# shield.net
KiCad netlist of a schematic drawn in EAGLE
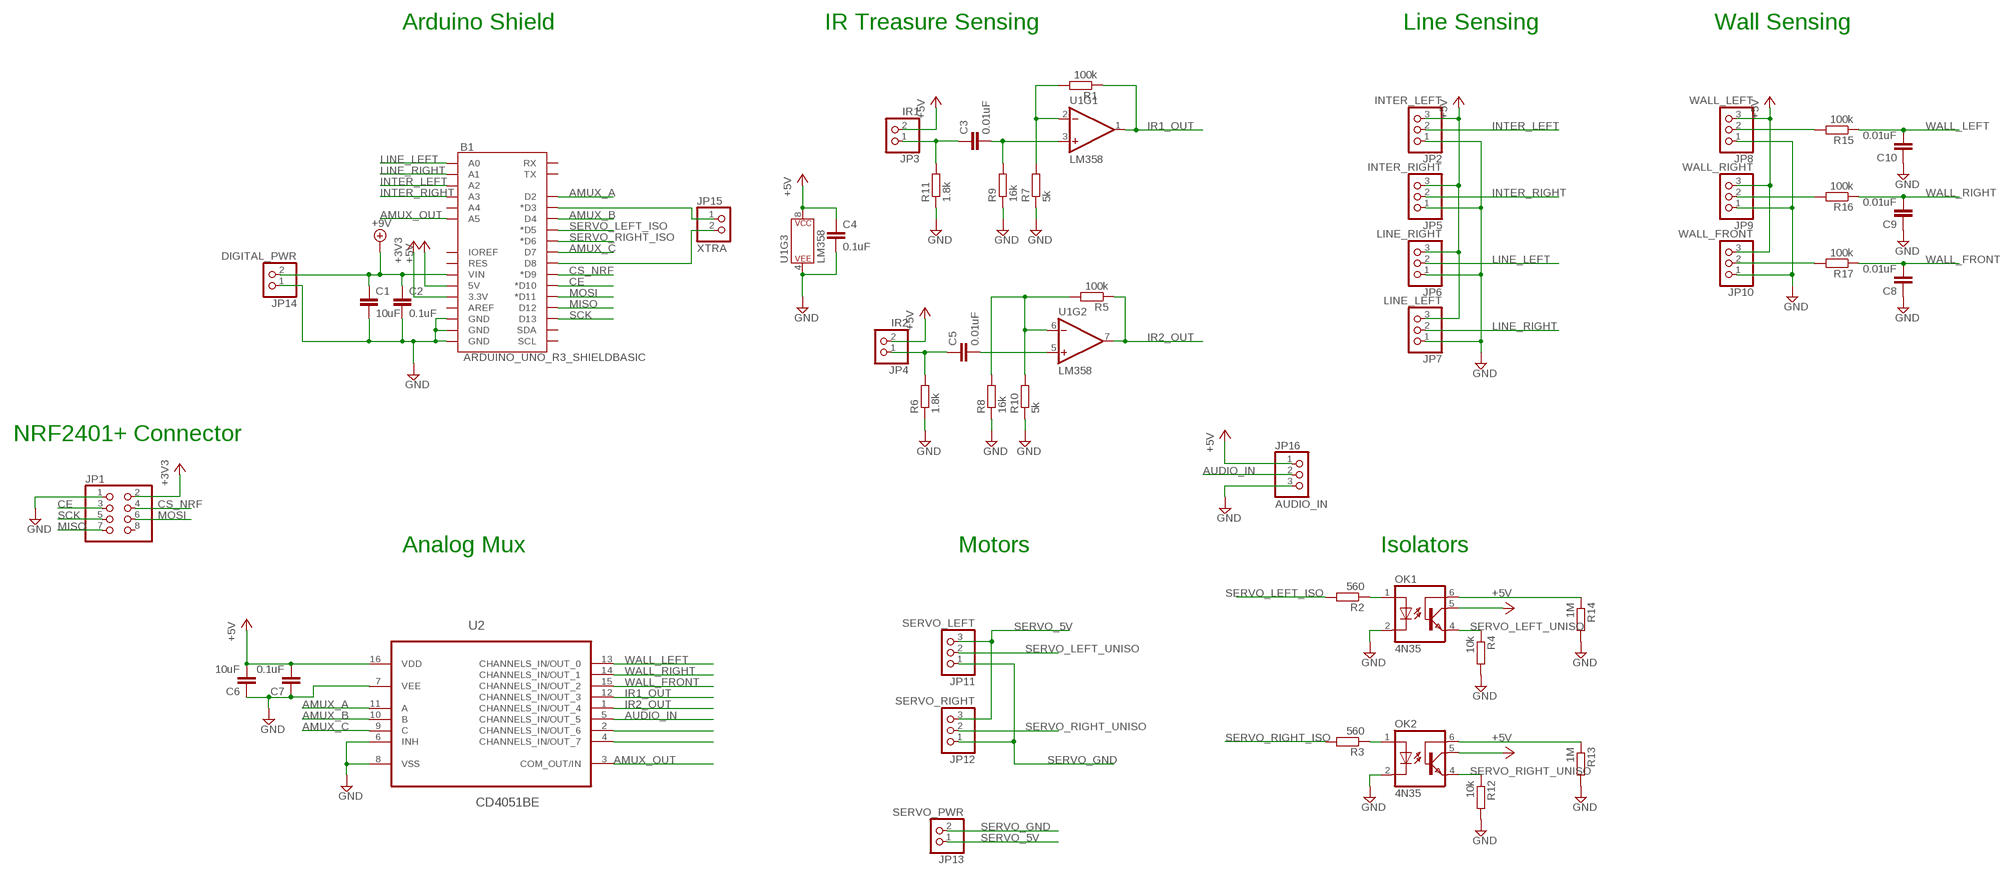
[diagram p0: schematic, sheet 1]

(export (version "E")
  (design (tool "Eeschema 10.0.6"))
  (components
    (comp (ref "B1")
      (value "ARDUINO_UNO_R3_SHIELDBASIC")
      (footprint "eagle-import:UNO_R3_SHIELD")
      (libsource (lib "eagle-import") (part "ARDUINO_UNO_R3_SHIELDBASIC"))
    )
    (comp (ref "C1")
      (value "10uF")
      (footprint "eagle-import:C5B3")
      (libsource (lib "eagle-import") (part "C5/3"))
    )
    (comp (ref "C2")
      (value "0.1uF")
      (footprint "eagle-import:C5B3")
      (libsource (lib "eagle-import") (part "C5/3"))
    )
    (comp (ref "C3")
      (value "0.01uF")
      (footprint "eagle-import:C5B3")
      (libsource (lib "eagle-import") (part "C5/3"))
    )
    (comp (ref "C4")
      (value "0.1uF")
      (footprint "eagle-import:C2.5-2")
      (libsource (lib "eagle-import") (part "C2.5/2"))
    )
    (comp (ref "C5")
      (value "0.01uF")
      (footprint "eagle-import:C5B3")
      (libsource (lib "eagle-import") (part "C5/3"))
    )
    (comp (ref "C6")
      (value "10uF")
      (footprint "eagle-import:C5B3")
      (libsource (lib "eagle-import") (part "C5/3"))
    )
    (comp (ref "C7")
      (value "0.1uF")
      (footprint "eagle-import:C5B3")
      (libsource (lib "eagle-import") (part "C5/3"))
    )
    (comp (ref "C8")
      (value "0.01uF")
      (footprint "eagle-import:C5B3")
      (libsource (lib "eagle-import") (part "C5/3"))
    )
    (comp (ref "C9")
      (value "0.01uF")
      (footprint "eagle-import:C5B3")
      (libsource (lib "eagle-import") (part "C5/3"))
    )
    (comp (ref "C10")
      (value "0.01uF")
      (footprint "eagle-import:C5B3")
      (libsource (lib "eagle-import") (part "C5/3"))
    )
    (comp (ref "JP1")
      (value "PINHD-2X4")
      (footprint "eagle-import:2X04")
      (libsource (lib "eagle-import") (part "PINHD-2X4"))
    )
    (comp (ref "JP2")
      (value "INTER_LEFT")
      (footprint "eagle-import:1X03")
      (libsource (lib "eagle-import") (part "PINHD-1X3"))
    )
    (comp (ref "JP3")
      (value "IR1")
      (footprint "eagle-import:1X02")
      (libsource (lib "eagle-import") (part "PINHD-1X2"))
    )
    (comp (ref "JP4")
      (value "IR2")
      (footprint "eagle-import:1X02")
      (libsource (lib "eagle-import") (part "PINHD-1X2"))
    )
    (comp (ref "JP5")
      (value "INTER_RIGHT")
      (footprint "eagle-import:1X03")
      (libsource (lib "eagle-import") (part "PINHD-1X3"))
    )
    (comp (ref "JP6")
      (value "LINE_RIGHT")
      (footprint "eagle-import:1X03")
      (libsource (lib "eagle-import") (part "PINHD-1X3"))
    )
    (comp (ref "JP7")
      (value "LINE_LEFT")
      (footprint "eagle-import:1X03")
      (libsource (lib "eagle-import") (part "PINHD-1X3"))
    )
    (comp (ref "JP8")
      (value "WALL_LEFT")
      (footprint "eagle-import:1X03")
      (libsource (lib "eagle-import") (part "PINHD-1X3"))
    )
    (comp (ref "JP9")
      (value "WALL_RIGHT")
      (footprint "eagle-import:1X03")
      (libsource (lib "eagle-import") (part "PINHD-1X3"))
    )
    (comp (ref "JP10")
      (value "WALL_FRONT")
      (footprint "eagle-import:1X03")
      (libsource (lib "eagle-import") (part "PINHD-1X3"))
    )
    (comp (ref "JP11")
      (value "SERVO_LEFT")
      (footprint "eagle-import:1X03")
      (libsource (lib "eagle-import") (part "PINHD-1X3"))
    )
    (comp (ref "JP12")
      (value "SERVO_RIGHT")
      (footprint "eagle-import:1X03")
      (libsource (lib "eagle-import") (part "PINHD-1X3"))
    )
    (comp (ref "JP13")
      (value "SERVO_PWR")
      (footprint "eagle-import:1X02")
      (libsource (lib "eagle-import") (part "PINHD-1X2"))
    )
    (comp (ref "JP14")
      (value "DIGITAL_PWR")
      (footprint "eagle-import:1X02")
      (libsource (lib "eagle-import") (part "PINHD-1X2"))
    )
    (comp (ref "JP15")
      (value "XTRA")
      (footprint "eagle-import:1X02")
      (libsource (lib "eagle-import") (part "PINHD-1X2"))
    )
    (comp (ref "JP16")
      (value "AUDIO_IN")
      (footprint "eagle-import:1X03")
      (libsource (lib "eagle-import") (part "PINHD-1X3"))
    )
    (comp (ref "OK1")
      (value "4N35")
      (footprint "eagle-import:DIL06")
      (fields (field (name "MF") "FAIRCHILD SEMICONDUCTOR"))
      (libsource (lib "eagle-import") (part "4N35"))
    )
    (comp (ref "OK2")
      (value "4N35")
      (footprint "eagle-import:DIL06")
      (fields (field (name "MF") "FAIRCHILD SEMICONDUCTOR"))
      (libsource (lib "eagle-import") (part "4N35"))
    )
    (comp (ref "R1")
      (value "100k")
      (footprint "eagle-import:VMTA55")
      (libsource (lib "eagle-import") (part "R-EU_VMTA55"))
    )
    (comp (ref "R2")
      (value "560")
      (footprint "eagle-import:VMTA55")
      (libsource (lib "eagle-import") (part "R-EU_VMTA55"))
    )
    (comp (ref "R3")
      (value "560")
      (footprint "eagle-import:VMTA55")
      (libsource (lib "eagle-import") (part "R-EU_VMTA55"))
    )
    (comp (ref "R4")
      (value "10k")
      (footprint "eagle-import:VMTA55")
      (libsource (lib "eagle-import") (part "R-EU_VMTA55"))
    )
    (comp (ref "R5")
      (value "100k")
      (footprint "eagle-import:VMTA55")
      (libsource (lib "eagle-import") (part "R-EU_VMTA55"))
    )
    (comp (ref "R6")
      (value "1.8k")
      (footprint "eagle-import:VMTA55")
      (libsource (lib "eagle-import") (part "R-EU_VMTA55"))
    )
    (comp (ref "R7")
      (value "5k")
      (footprint "eagle-import:VMTA55")
      (libsource (lib "eagle-import") (part "R-EU_VMTA55"))
    )
    (comp (ref "R8")
      (value "16k")
      (footprint "eagle-import:VMTA55")
      (libsource (lib "eagle-import") (part "R-EU_VMTA55"))
    )
    (comp (ref "R9")
      (value "16k")
      (footprint "eagle-import:VMTA55")
      (libsource (lib "eagle-import") (part "R-EU_VMTA55"))
    )
    (comp (ref "R10")
      (value "5k")
      (footprint "eagle-import:VMTA55")
      (libsource (lib "eagle-import") (part "R-EU_VMTA55"))
    )
    (comp (ref "R11")
      (value "1.8k")
      (footprint "eagle-import:VMTA55")
      (libsource (lib "eagle-import") (part "R-EU_VMTA55"))
    )
    (comp (ref "R12")
      (value "10k")
      (footprint "eagle-import:VMTA55")
      (libsource (lib "eagle-import") (part "R-EU_VMTA55"))
    )
    (comp (ref "R13")
      (value "1M")
      (footprint "eagle-import:VMTA55")
      (libsource (lib "eagle-import") (part "R-EU_VMTA55"))
    )
    (comp (ref "R14")
      (value "1M")
      (footprint "eagle-import:VMTA55")
      (libsource (lib "eagle-import") (part "R-EU_VMTA55"))
    )
    (comp (ref "R15")
      (value "100k")
      (footprint "eagle-import:VMTA55")
      (libsource (lib "eagle-import") (part "R-EU_VMTA55"))
    )
    (comp (ref "R16")
      (value "100k")
      (footprint "eagle-import:VMTA55")
      (libsource (lib "eagle-import") (part "R-EU_VMTA55"))
    )
    (comp (ref "R17")
      (value "100k")
      (footprint "eagle-import:VMTA55")
      (libsource (lib "eagle-import") (part "R-EU_VMTA55"))
    )
    (comp (ref "U1")
      (value "LM358")
      (footprint "eagle-import:DIP08")
      (libsource (lib "eagle-import") (part "LM358"))
    )
    (comp (ref "U2")
      (value "CD4051BE")
      (footprint "eagle-import:DIP254P762X508-16")
      (libsource (lib "eagle-import") (part "CD4051BE"))
    )
  )
  (nets
    (net (code "1") (name "+3V3") (class "Default")
      (node (ref "B1") (pin "3.3V") (pinfunction "3.3V_3.3V") (pintype "bidirectional"))
      (node (ref "JP1") (pin "2") (pinfunction "2_2") (pintype "passive"))
    )
    (net (code "2") (name "+5V") (class "Default")
      (node (ref "B1") (pin "5V") (pinfunction "5V_5V") (pintype "bidirectional"))
      (node (ref "C4") (pin "1") (pinfunction "1_1") (pintype "passive"))
      (node (ref "C6") (pin "2") (pinfunction "2_2") (pintype "passive"))
      (node (ref "C7") (pin "2") (pinfunction "2_2") (pintype "passive"))
      (node (ref "JP10") (pin "3") (pinfunction "3_3") (pintype "passive"))
      (node (ref "JP16") (pin "1") (pinfunction "1_1") (pintype "passive"))
      (node (ref "JP2") (pin "3") (pinfunction "3_3") (pintype "passive"))
      (node (ref "JP3") (pin "2") (pinfunction "2_2") (pintype "passive"))
      (node (ref "JP4") (pin "2") (pinfunction "2_2") (pintype "passive"))
      (node (ref "JP5") (pin "3") (pinfunction "3_3") (pintype "passive"))
      (node (ref "JP6") (pin "3") (pinfunction "3_3") (pintype "passive"))
      (node (ref "JP7") (pin "3") (pinfunction "3_3") (pintype "passive"))
      (node (ref "JP8") (pin "3") (pinfunction "3_3") (pintype "passive"))
      (node (ref "JP9") (pin "3") (pinfunction "3_3") (pintype "passive"))
      (node (ref "OK1") (pin "5") (pinfunction "COL_5") (pintype "passive"))
      (node (ref "OK2") (pin "5") (pinfunction "COL_5") (pintype "passive"))
      (node (ref "U1") (pin "8") (pinfunction "P$V+_8") (pintype "bidirectional"))
      (node (ref "U2") (pin "16") (pinfunction "VDD_16") (pintype "power_in"))
    )
    (net (code "3") (name "+9V") (class "Default")
      (node (ref "B1") (pin "VIN") (pinfunction "VIN_VIN") (pintype "bidirectional"))
      (node (ref "C1") (pin "1") (pinfunction "1_1") (pintype "passive"))
      (node (ref "C2") (pin "1") (pinfunction "1_1") (pintype "passive"))
      (node (ref "JP14") (pin "2") (pinfunction "2_2") (pintype "passive"))
    )
    (net (code "4") (name "/AMUX_A") (class "Default")
      (node (ref "B1") (pin "D2") (pinfunction "D2_D2") (pintype "bidirectional"))
      (node (ref "U2") (pin "11") (pinfunction "A_11") (pintype "input"))
    )
    (net (code "5") (name "/AMUX_B") (class "Default")
      (node (ref "B1") (pin "D4") (pinfunction "D4_D4") (pintype "bidirectional"))
      (node (ref "U2") (pin "10") (pinfunction "B_10") (pintype "input"))
    )
    (net (code "6") (name "/AMUX_C") (class "Default")
      (node (ref "B1") (pin "D7") (pinfunction "D7_D7") (pintype "bidirectional"))
      (node (ref "U2") (pin "9") (pinfunction "C_9") (pintype "input"))
    )
    (net (code "7") (name "/AMUX_OUT") (class "Default")
      (node (ref "B1") (pin "A5") (pinfunction "A5_A5") (pintype "bidirectional"))
      (node (ref "U2") (pin "3") (pinfunction "COM_OUT/IN_3") (pintype "bidirectional"))
    )
    (net (code "8") (name "/AUDIO_IN") (class "Default")
      (node (ref "JP16") (pin "2") (pinfunction "2_2") (pintype "passive"))
      (node (ref "U2") (pin "5") (pinfunction "CHANNELS_IN/OUT_5_5") (pintype "bidirectional"))
    )
    (net (code "9") (name "/CE") (class "Default")
      (node (ref "B1") (pin "D10") (pinfunction "*D10_D10") (pintype "bidirectional"))
      (node (ref "JP1") (pin "3") (pinfunction "3_3") (pintype "passive"))
    )
    (net (code "10") (name "/CS_NRF") (class "Default")
      (node (ref "B1") (pin "D9") (pinfunction "*D9_D9") (pintype "bidirectional"))
      (node (ref "JP1") (pin "4") (pinfunction "4_4") (pintype "passive"))
    )
    (net (code "11") (name "/INTER_LEFT") (class "Default")
      (node (ref "B1") (pin "A2") (pinfunction "A2_A2") (pintype "bidirectional"))
      (node (ref "JP2") (pin "2") (pinfunction "2_2") (pintype "passive"))
    )
    (net (code "12") (name "/INTER_RIGHT") (class "Default")
      (node (ref "B1") (pin "A3") (pinfunction "A3_A3") (pintype "bidirectional"))
      (node (ref "JP5") (pin "2") (pinfunction "2_2") (pintype "passive"))
    )
    (net (code "13") (name "/IR1_OUT") (class "Default")
      (node (ref "R1") (pin "1") (pinfunction "1_1") (pintype "passive"))
      (node (ref "U1") (pin "1") (pinfunction "OUT_1") (pintype "output"))
      (node (ref "U2") (pin "12") (pinfunction "CHANNELS_IN/OUT_3_12") (pintype "bidirectional"))
    )
    (net (code "14") (name "/IR2_OUT") (class "Default")
      (node (ref "R5") (pin "1") (pinfunction "1_1") (pintype "passive"))
      (node (ref "U1") (pin "7") (pinfunction "OUT_7") (pintype "output"))
      (node (ref "U2") (pin "1") (pinfunction "CHANNELS_IN/OUT_4_1") (pintype "bidirectional"))
    )
    (net (code "15") (name "/LINE_LEFT") (class "Default")
      (node (ref "B1") (pin "A0") (pinfunction "A0_A0") (pintype "bidirectional"))
      (node (ref "JP6") (pin "2") (pinfunction "2_2") (pintype "passive"))
    )
    (net (code "16") (name "/LINE_RIGHT") (class "Default")
      (node (ref "B1") (pin "A1") (pinfunction "A1_A1") (pintype "bidirectional"))
      (node (ref "JP7") (pin "2") (pinfunction "2_2") (pintype "passive"))
    )
    (net (code "17") (name "/MISO") (class "Default")
      (node (ref "B1") (pin "D12") (pinfunction "D12_D12") (pintype "bidirectional"))
      (node (ref "JP1") (pin "7") (pinfunction "7_7") (pintype "passive"))
    )
    (net (code "18") (name "/MOSI") (class "Default")
      (node (ref "B1") (pin "D11") (pinfunction "*D11_D11") (pintype "bidirectional"))
      (node (ref "JP1") (pin "6") (pinfunction "6_6") (pintype "passive"))
    )
    (net (code "19") (name "/SCK") (class "Default")
      (node (ref "B1") (pin "D13") (pinfunction "D13_D13") (pintype "bidirectional"))
      (node (ref "JP1") (pin "5") (pinfunction "5_5") (pintype "passive"))
    )
    (net (code "20") (name "/SERVO_5V") (class "Default")
      (node (ref "JP11") (pin "3") (pinfunction "3_3") (pintype "passive"))
      (node (ref "JP12") (pin "3") (pinfunction "3_3") (pintype "passive"))
      (node (ref "JP13") (pin "1") (pinfunction "1_1") (pintype "passive"))
    )
    (net (code "21") (name "/SERVO_GND") (class "Default")
      (node (ref "JP11") (pin "1") (pinfunction "1_1") (pintype "passive"))
      (node (ref "JP12") (pin "1") (pinfunction "1_1") (pintype "passive"))
      (node (ref "JP13") (pin "2") (pinfunction "2_2") (pintype "passive"))
    )
    (net (code "22") (name "/SERVO_LEFT_ISO") (class "Default")
      (node (ref "B1") (pin "D5") (pinfunction "*D5_D5") (pintype "bidirectional"))
      (node (ref "R2") (pin "2") (pinfunction "2_2") (pintype "passive"))
    )
    (net (code "23") (name "/SERVO_LEFT_UNISO") (class "Default")
      (node (ref "JP11") (pin "2") (pinfunction "2_2") (pintype "passive"))
      (node (ref "OK1") (pin "4") (pinfunction "EMI_4") (pintype "passive"))
      (node (ref "R4") (pin "1") (pinfunction "1_1") (pintype "passive"))
    )
    (net (code "24") (name "/SERVO_RIGHT_ISO") (class "Default")
      (node (ref "B1") (pin "D6") (pinfunction "*D6_D6") (pintype "bidirectional"))
      (node (ref "R3") (pin "2") (pinfunction "2_2") (pintype "passive"))
    )
    (net (code "25") (name "/SERVO_RIGHT_UNISO") (class "Default")
      (node (ref "JP12") (pin "2") (pinfunction "2_2") (pintype "passive"))
      (node (ref "OK2") (pin "4") (pinfunction "EMI_4") (pintype "passive"))
      (node (ref "R12") (pin "1") (pinfunction "1_1") (pintype "passive"))
    )
    (net (code "26") (name "/WALL_FRONT") (class "Default")
      (node (ref "C8") (pin "2") (pinfunction "2_2") (pintype "passive"))
      (node (ref "R17") (pin "1") (pinfunction "1_1") (pintype "passive"))
      (node (ref "U2") (pin "15") (pinfunction "CHANNELS_IN/OUT_2_15") (pintype "bidirectional"))
    )
    (net (code "27") (name "/WALL_LEFT") (class "Default")
      (node (ref "C10") (pin "2") (pinfunction "2_2") (pintype "passive"))
      (node (ref "R15") (pin "1") (pinfunction "1_1") (pintype "passive"))
      (node (ref "U2") (pin "13") (pinfunction "CHANNELS_IN/OUT_0_13") (pintype "bidirectional"))
    )
    (net (code "28") (name "/WALL_RIGHT") (class "Default")
      (node (ref "C9") (pin "2") (pinfunction "2_2") (pintype "passive"))
      (node (ref "R16") (pin "1") (pinfunction "1_1") (pintype "passive"))
      (node (ref "U2") (pin "14") (pinfunction "CHANNELS_IN/OUT_1_14") (pintype "bidirectional"))
    )
    (net (code "29") (name "GND") (class "Default")
      (node (ref "B1") (pin "GND@0") (pinfunction "GND_GND@0") (pintype "bidirectional"))
      (node (ref "B1") (pin "GND@1") (pinfunction "GND_GND@1") (pintype "bidirectional"))
      (node (ref "B1") (pin "GND@2") (pinfunction "GND_GND@2") (pintype "bidirectional"))
      (node (ref "C1") (pin "2") (pinfunction "2_2") (pintype "passive"))
      (node (ref "C10") (pin "1") (pinfunction "1_1") (pintype "passive"))
      (node (ref "C2") (pin "2") (pinfunction "2_2") (pintype "passive"))
      (node (ref "C4") (pin "2") (pinfunction "2_2") (pintype "passive"))
      (node (ref "C6") (pin "1") (pinfunction "1_1") (pintype "passive"))
      (node (ref "C7") (pin "1") (pinfunction "1_1") (pintype "passive"))
      (node (ref "C8") (pin "1") (pinfunction "1_1") (pintype "passive"))
      (node (ref "C9") (pin "1") (pinfunction "1_1") (pintype "passive"))
      (node (ref "JP1") (pin "1") (pinfunction "1_1") (pintype "passive"))
      (node (ref "JP10") (pin "1") (pinfunction "1_1") (pintype "passive"))
      (node (ref "JP14") (pin "1") (pinfunction "1_1") (pintype "passive"))
      (node (ref "JP16") (pin "3") (pinfunction "3_3") (pintype "passive"))
      (node (ref "JP2") (pin "1") (pinfunction "1_1") (pintype "passive"))
      (node (ref "JP5") (pin "1") (pinfunction "1_1") (pintype "passive"))
      (node (ref "JP6") (pin "1") (pinfunction "1_1") (pintype "passive"))
      (node (ref "JP7") (pin "1") (pinfunction "1_1") (pintype "passive"))
      (node (ref "JP8") (pin "1") (pinfunction "1_1") (pintype "passive"))
      (node (ref "JP9") (pin "1") (pinfunction "1_1") (pintype "passive"))
      (node (ref "OK1") (pin "2") (pinfunction "C_2") (pintype "passive"))
      (node (ref "OK2") (pin "2") (pinfunction "C_2") (pintype "passive"))
      (node (ref "R10") (pin "1") (pinfunction "1_1") (pintype "passive"))
      (node (ref "R11") (pin "1") (pinfunction "1_1") (pintype "passive"))
      (node (ref "R12") (pin "2") (pinfunction "2_2") (pintype "passive"))
      (node (ref "R13") (pin "2") (pinfunction "2_2") (pintype "passive"))
      (node (ref "R14") (pin "2") (pinfunction "2_2") (pintype "passive"))
      (node (ref "R4") (pin "2") (pinfunction "2_2") (pintype "passive"))
      (node (ref "R6") (pin "1") (pinfunction "1_1") (pintype "passive"))
      (node (ref "R7") (pin "1") (pinfunction "1_1") (pintype "passive"))
      (node (ref "R8") (pin "1") (pinfunction "1_1") (pintype "passive"))
      (node (ref "R9") (pin "1") (pinfunction "1_1") (pintype "passive"))
      (node (ref "U1") (pin "4") (pinfunction "P$V-_4") (pintype "bidirectional"))
      (node (ref "U2") (pin "6") (pinfunction "INH_6") (pintype "input"))
      (node (ref "U2") (pin "7") (pinfunction "VEE_7") (pintype "power_in"))
      (node (ref "U2") (pin "8") (pinfunction "VSS_8") (pintype "power_in"))
    )
    (net (code "30") (name "Net-(B1-*D3)") (class "Default")
      (node (ref "B1") (pin "D3") (pinfunction "*D3_D3") (pintype "bidirectional"))
      (node (ref "JP15") (pin "1") (pinfunction "1_1") (pintype "passive"))
    )
    (net (code "31") (name "Net-(B1-PadD8)") (class "Default")
      (node (ref "B1") (pin "D8") (pinfunction "D8_D8") (pintype "bidirectional"))
      (node (ref "JP15") (pin "2") (pinfunction "2_2") (pintype "passive"))
    )
    (net (code "32") (name "Net-(C3-Pad1)") (class "Default")
      (node (ref "C3") (pin "1") (pinfunction "1_1") (pintype "passive"))
      (node (ref "JP3") (pin "1") (pinfunction "1_1") (pintype "passive"))
      (node (ref "R11") (pin "2") (pinfunction "2_2") (pintype "passive"))
    )
    (net (code "33") (name "Net-(C5-Pad1)") (class "Default")
      (node (ref "C5") (pin "1") (pinfunction "1_1") (pintype "passive"))
      (node (ref "JP4") (pin "1") (pinfunction "1_1") (pintype "passive"))
      (node (ref "R6") (pin "2") (pinfunction "2_2") (pintype "passive"))
    )
    (net (code "34") (name "Net-(JP8-Pad2)") (class "Default")
      (node (ref "JP8") (pin "2") (pinfunction "2_2") (pintype "passive"))
      (node (ref "R15") (pin "2") (pinfunction "2_2") (pintype "passive"))
    )
    (net (code "35") (name "Net-(JP9-Pad2)") (class "Default")
      (node (ref "JP9") (pin "2") (pinfunction "2_2") (pintype "passive"))
      (node (ref "R16") (pin "2") (pinfunction "2_2") (pintype "passive"))
    )
    (net (code "36") (name "Net-(JP10-Pad2)") (class "Default")
      (node (ref "JP10") (pin "2") (pinfunction "2_2") (pintype "passive"))
      (node (ref "R17") (pin "2") (pinfunction "2_2") (pintype "passive"))
    )
    (net (code "37") (name "Net-(OK1-A)") (class "Default")
      (node (ref "OK1") (pin "1") (pinfunction "A_1") (pintype "passive"))
      (node (ref "R2") (pin "1") (pinfunction "1_1") (pintype "passive"))
    )
    (net (code "38") (name "Net-(OK1-BAS)") (class "Default")
      (node (ref "OK1") (pin "6") (pinfunction "BAS_6") (pintype "passive"))
      (node (ref "R14") (pin "1") (pinfunction "1_1") (pintype "passive"))
    )
    (net (code "39") (name "Net-(OK2-A)") (class "Default")
      (node (ref "OK2") (pin "1") (pinfunction "A_1") (pintype "passive"))
      (node (ref "R3") (pin "1") (pinfunction "1_1") (pintype "passive"))
    )
    (net (code "40") (name "Net-(OK2-BAS)") (class "Default")
      (node (ref "OK2") (pin "6") (pinfunction "BAS_6") (pintype "passive"))
      (node (ref "R13") (pin "1") (pinfunction "1_1") (pintype "passive"))
    )
    (net (code "41") (name "Net-(U1A-+IN)") (class "Default")
      (node (ref "C3") (pin "2") (pinfunction "2_2") (pintype "passive"))
      (node (ref "R9") (pin "2") (pinfunction "2_2") (pintype "passive"))
      (node (ref "U1") (pin "3") (pinfunction "+IN_3") (pintype "input"))
    )
    (net (code "42") (name "Net-(U1A--IN)") (class "Default")
      (node (ref "R1") (pin "2") (pinfunction "2_2") (pintype "passive"))
      (node (ref "R7") (pin "2") (pinfunction "2_2") (pintype "passive"))
      (node (ref "U1") (pin "2") (pinfunction "-IN_2") (pintype "input"))
    )
    (net (code "43") (name "Net-(U1B-+IN)") (class "Default")
      (node (ref "C5") (pin "2") (pinfunction "2_2") (pintype "passive"))
      (node (ref "U1") (pin "5") (pinfunction "+IN_5") (pintype "input"))
    )
    (net (code "44") (name "Net-(U1B--IN)") (class "Default")
      (node (ref "R10") (pin "2") (pinfunction "2_2") (pintype "passive"))
      (node (ref "R5") (pin "2") (pinfunction "2_2") (pintype "passive"))
      (node (ref "R8") (pin "2") (pinfunction "2_2") (pintype "passive"))
      (node (ref "U1") (pin "6") (pinfunction "-IN_6") (pintype "input"))
    )
    (net (code "45") (name "unconnected-(B1-PadA4)") (class "Default")
      (node (ref "B1") (pin "A4") (pinfunction "A4_A4") (pintype "bidirectional"))
    )
    (net (code "46") (name "unconnected-(B1-PadAREF)") (class "Default")
      (node (ref "B1") (pin "AREF") (pinfunction "AREF_AREF") (pintype "bidirectional"))
    )
    (net (code "47") (name "unconnected-(B1-PadIOREF)") (class "Default")
      (node (ref "B1") (pin "IOREF") (pinfunction "IOREF_IOREF") (pintype "bidirectional"))
    )
    (net (code "48") (name "unconnected-(B1-PadRES)") (class "Default")
      (node (ref "B1") (pin "RES") (pinfunction "RES_RES") (pintype "bidirectional"))
    )
    (net (code "49") (name "unconnected-(B1-PadRX)") (class "Default")
      (node (ref "B1") (pin "RX") (pinfunction "RX_RX") (pintype "bidirectional"))
    )
    (net (code "50") (name "unconnected-(B1-PadSCL)") (class "Default")
      (node (ref "B1") (pin "SCL") (pinfunction "SCL_SCL") (pintype "bidirectional"))
    )
    (net (code "51") (name "unconnected-(B1-PadSDA)") (class "Default")
      (node (ref "B1") (pin "SDA") (pinfunction "SDA_SDA") (pintype "bidirectional"))
    )
    (net (code "52") (name "unconnected-(B1-PadTX)") (class "Default")
      (node (ref "B1") (pin "TX") (pinfunction "TX_TX") (pintype "bidirectional"))
    )
    (net (code "53") (name "unconnected-(JP1-Pad8)") (class "Default")
      (node (ref "JP1") (pin "8") (pinfunction "8_8") (pintype "passive"))
    )
    (net (code "54") (name "unconnected-(U2-CHANNELS_IN{slash}OUT_6-Pad2)") (class "Default")
      (node (ref "U2") (pin "2") (pinfunction "CHANNELS_IN/OUT_6_2") (pintype "bidirectional"))
    )
    (net (code "55") (name "unconnected-(U2-CHANNELS_IN{slash}OUT_7-Pad4)") (class "Default")
      (node (ref "U2") (pin "4") (pinfunction "CHANNELS_IN/OUT_7_4") (pintype "bidirectional"))
    )
  )
)
